# Motor_Driver.net
KiCad netlist of a schematic drawn in Altium Designer
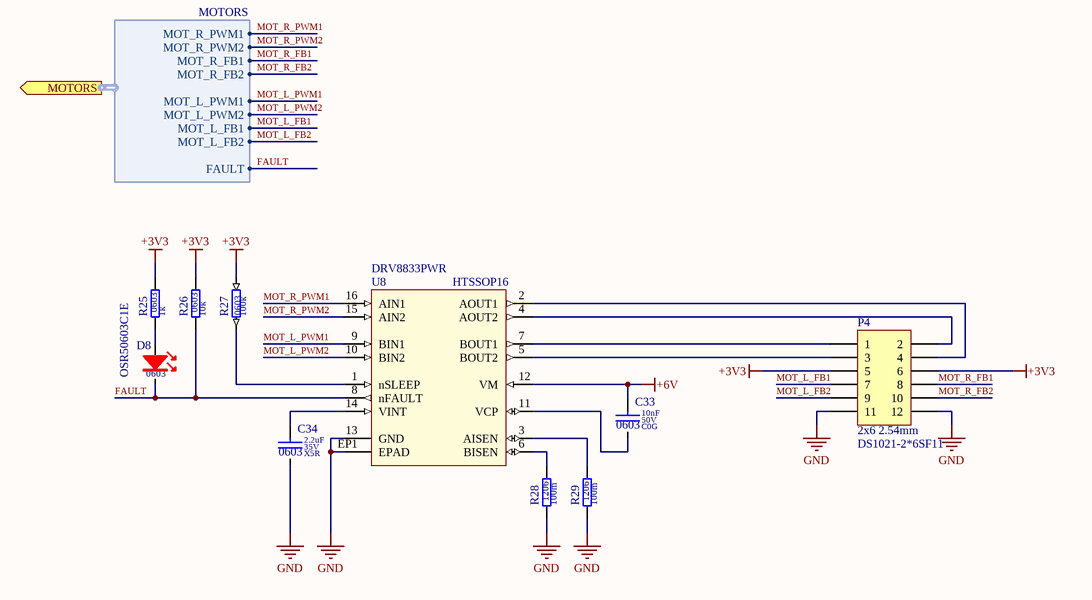
[diagram p0: Motor Driver.SchDoc]

(export (version "E")
  (design (tool "Eeschema 10.0.6"))
  (components
    (comp (ref "C33")
      (value "10nF")
      (footprint "C_0603_1608")
      (description "Capacitor")
      (fields
        (field (name "DIELECTRIC") "C0G")
        (field (name "VOLTAGE") "50V")
        (field (name "SCH_FOOTPRINT") "0603")
        (field (name "PART NUMBER") "C_10nF_50V_C0G_0603_5")
        (field (name "MANUFACTURER") "Murata")
      )
      (libsource (lib "Library") (part "C"))
    )
    (comp (ref "C34")
      (value "2.2uF")
      (footprint "C_0603_1608")
      (description "Capacitor")
      (fields
        (field (name "DIELECTRIC") "X5R")
        (field (name "VOLTAGE") "35V")
        (field (name "SCH_FOOTPRINT") "0603")
        (field (name "PART NUMBER") "C_2.2uF_35V_X5R_0603_10")
        (field (name "MANUFACTURER") "Murata")
      )
      (libsource (lib "Library") (part "C"))
    )
    (comp (ref "D8")
      (value "OSR50603C1E")
      (footprint "OL_0603_1608")
      (description "LED_RED")
      (fields
        (field (name "SCH_FOOTPRINT") "0603")
        (field (name "PART NUMBER") "OL_R_0603_OSR50603C1E")
        (field (name "MANUFACTURER") "Optosupply")
      )
      (libsource (lib "Library") (part "OL_R"))
    )
    (comp (ref "P4")
      (value "DS1021-2*6SF11")
      (footprint "P_HEADER_2x6_2.54")
      (description "Pin Header")
      (fields
        (field (name "SCH_FOOTPRINT") "2x6 2.54mm")
        (field (name "PART NUMBER") "P_HEADER_2x6_2.54")
        (field (name "MANUFACTURER") "Connfly")
      )
      (libsource (lib "Library") (part "P_HEADER_2x6"))
    )
    (comp (ref "R25")
      (value "1k")
      (footprint "R_0603_1608")
      (fields
        (field (name "SCH_FOOTPRINT") "0603")
        (field (name "PART NUMBER") "R_1k_0603_1")
        (field (name "VOLTAGE") "75V")
        (field (name "POWER") "100mW")
      )
      (libsource (lib "Library") (part "R"))
    )
    (comp (ref "R26")
      (value "10k")
      (footprint "R_0603_1608")
      (fields
        (field (name "SCH_FOOTPRINT") "0603")
        (field (name "PART NUMBER") "R_10k_0603_1")
        (field (name "VOLTAGE") "75V")
        (field (name "POWER") "100mW")
      )
      (libsource (lib "Library") (part "R"))
    )
    (comp (ref "R27")
      (value "100k")
      (footprint "R_0603_1608")
      (fields
        (field (name "SCH_FOOTPRINT") "0603")
        (field (name "PART NUMBER") "R_100k_0603_1")
        (field (name "VOLTAGE") "50V")
        (field (name "POWER") "100mW")
      )
      (libsource (lib "") (part "R_1"))
    )
    (comp (ref "R28")
      (value "100m")
      (footprint "R_1206_3216")
      (fields
        (field (name "SCH_FOOTPRINT") "1206")
        (field (name "PART NUMBER") "R_100m_1206_1")
        (field (name "VOLTAGE") "316mV")
        (field (name "POWER") "1W")
      )
      (libsource (lib "Library") (part "R"))
    )
    (comp (ref "R29")
      (value "100m")
      (footprint "R_1206_3216")
      (fields
        (field (name "SCH_FOOTPRINT") "1206")
        (field (name "PART NUMBER") "R_100m_1206_1")
        (field (name "VOLTAGE") "316mV")
        (field (name "POWER") "1W")
      )
      (libsource (lib "Library") (part "R"))
    )
    (comp (ref "U8")
      (value "DRV8833PWR")
      (footprint "HTSSOP16_45x66x20_M")
      (fields
        (field (name "SCH_FOOTPRINT") "HTSSOP16")
        (field (name "PART NUMBER") "U_DRV8833PWR")
        (field (name "MANUFACTURER") "Texas Instruments")
        (field (name "Comment") "2A Low Voltage Dual Brushed DC or Single Bipolar Stepper Motor Driver (PWM Ctrl)")
      )
      (libsource (lib "Library") (part "U_DRV8833_HTSSOP_TSSOP"))
    )
  )
  (nets
    (net (code "2") (name "+3V3") (class "Default")
      (node (ref "P4") (pin "5") (pinfunction "5_5") (pintype "passive"))
      (node (ref "P4") (pin "6") (pinfunction "6_6") (pintype "passive"))
      (node (ref "R25") (pin "2") (pinfunction "2_2") (pintype "passive"))
      (node (ref "R26") (pin "2") (pinfunction "2_2") (pintype "passive"))
      (node (ref "R27") (pin "1") (pinfunction "1_1") (pintype "input"))
    )
    (net (code "3") (name "+6V") (class "Default")
      (node (ref "C33") (pin "1") (pinfunction "1_1") (pintype "passive"))
      (node (ref "U8") (pin "12") (pinfunction "VM_12") (pintype "input"))
    )
    (net (code "4") (name "/FAULT") (class "Default")
      (node (ref "D8") (pin "1") (pinfunction "K_1") (pintype "passive"))
      (node (ref "R26") (pin "1") (pinfunction "1_1") (pintype "passive"))
      (node (ref "U8") (pin "8") (pinfunction "nFAULT_8") (pintype "output"))
    )
    (net (code "5") (name "/MOT_L_FB1") (class "Default")
      (node (ref "P4") (pin "7") (pinfunction "7_7") (pintype "passive"))
    )
    (net (code "6") (name "/MOT_L_FB2") (class "Default")
      (node (ref "P4") (pin "9") (pinfunction "9_9") (pintype "passive"))
    )
    (net (code "7") (name "/MOT_L_PWM1") (class "Default")
      (node (ref "U8") (pin "9") (pinfunction "BIN1_9") (pintype "input"))
    )
    (net (code "8") (name "/MOT_L_PWM2") (class "Default")
      (node (ref "U8") (pin "10") (pinfunction "BIN2_10") (pintype "input"))
    )
    (net (code "9") (name "/MOT_R_FB1") (class "Default")
      (node (ref "P4") (pin "8") (pinfunction "8_8") (pintype "passive"))
    )
    (net (code "10") (name "/MOT_R_FB2") (class "Default")
      (node (ref "P4") (pin "10") (pinfunction "10_10") (pintype "passive"))
    )
    (net (code "11") (name "/MOT_R_PWM1") (class "Default")
      (node (ref "U8") (pin "16") (pinfunction "AIN1_16") (pintype "input"))
    )
    (net (code "12") (name "/MOT_R_PWM2") (class "Default")
      (node (ref "U8") (pin "15") (pinfunction "AIN2_15") (pintype "input"))
    )
    (net (code "14") (name "GND") (class "Default")
      (node (ref "C34") (pin "2") (pinfunction "2_2") (pintype "passive"))
      (node (ref "P4") (pin "11") (pinfunction "11_11") (pintype "passive"))
      (node (ref "P4") (pin "12") (pinfunction "12_12") (pintype "passive"))
      (node (ref "R28") (pin "1") (pinfunction "1_1") (pintype "passive"))
      (node (ref "R29") (pin "1") (pinfunction "1_1") (pintype "passive"))
      (node (ref "U8") (pin "13") (pinfunction "GND_13") (pintype "power_in"))
      (node (ref "U8") (pin "EP1") (pinfunction "EPAD_EP1") (pintype "power_in"))
    )
    (net (code "15") (name "Net-(D8-A)") (class "Default")
      (node (ref "D8") (pin "2") (pinfunction "A_2") (pintype "passive"))
      (node (ref "R25") (pin "1") (pinfunction "1_1") (pintype "passive"))
    )
    (net (code "16") (name "Net-(U8-AISEN)") (class "Default")
      (node (ref "R29") (pin "2") (pinfunction "2_2") (pintype "passive"))
      (node (ref "U8") (pin "3") (pinfunction "AISEN_3") (pintype "bidirectional"))
    )
    (net (code "17") (name "Net-(U8-AOUT1)") (class "Default")
      (node (ref "P4") (pin "4") (pinfunction "4_4") (pintype "passive"))
      (node (ref "U8") (pin "2") (pinfunction "AOUT1_2") (pintype "output"))
    )
    (net (code "18") (name "Net-(U8-AOUT2)") (class "Default")
      (node (ref "P4") (pin "2") (pinfunction "2_2") (pintype "passive"))
      (node (ref "U8") (pin "4") (pinfunction "AOUT2_4") (pintype "output"))
    )
    (net (code "19") (name "Net-(U8-BISEN)") (class "Default")
      (node (ref "R28") (pin "2") (pinfunction "2_2") (pintype "passive"))
      (node (ref "U8") (pin "6") (pinfunction "BISEN_6") (pintype "bidirectional"))
    )
    (net (code "20") (name "Net-(U8-BOUT1)") (class "Default")
      (node (ref "P4") (pin "1") (pinfunction "1_1") (pintype "passive"))
      (node (ref "U8") (pin "7") (pinfunction "BOUT1_7") (pintype "output"))
    )
    (net (code "21") (name "Net-(U8-BOUT2)") (class "Default")
      (node (ref "P4") (pin "3") (pinfunction "3_3") (pintype "passive"))
      (node (ref "U8") (pin "5") (pinfunction "BOUT2_5") (pintype "output"))
    )
    (net (code "22") (name "Net-(U8-VCP)") (class "Default")
      (node (ref "C33") (pin "2") (pinfunction "2_2") (pintype "passive"))
      (node (ref "U8") (pin "11") (pinfunction "VCP_11") (pintype "bidirectional"))
    )
    (net (code "23") (name "Net-(U8-VINT)") (class "Default")
      (node (ref "C34") (pin "1") (pinfunction "1_1") (pintype "passive"))
      (node (ref "U8") (pin "14") (pinfunction "VINT_14") (pintype "input"))
    )
    (net (code "24") (name "Net-(U8-nSLEEP)") (class "Default")
      (node (ref "R27") (pin "2") (pinfunction "2_2") (pintype "output"))
      (node (ref "U8") (pin "1") (pinfunction "nSLEEP_1") (pintype "input"))
    )
  )
)
